# mcu.net
KiCad netlist of a schematic drawn in Altium Designer
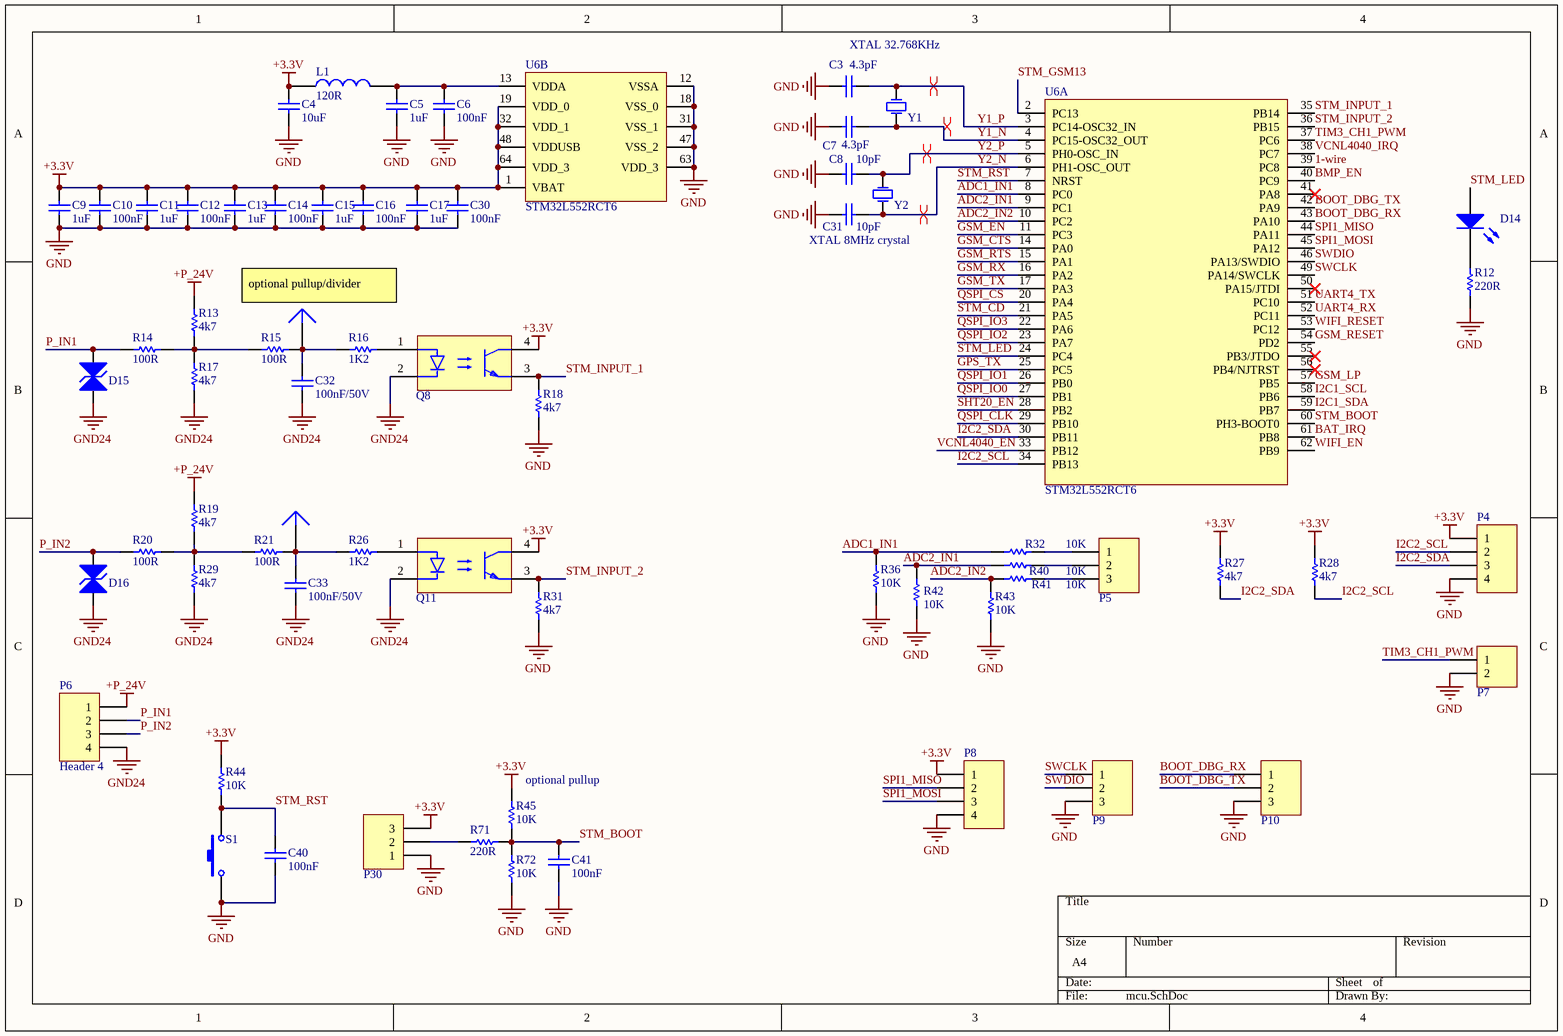
[diagram p0: mcu.SchDoc]

(export (version "E")
  (design (tool "Eeschema 10.0.6"))
  (components
    (comp (ref "C3")
      (value "4.3pF")
      (footprint "C0402")
      (description "Capacitor")
      (fields (field (name "Comment") "Cap 4.3pF"))
      (libsource (lib "integratedLib") (part "Cap 4.3pF"))
    )
    (comp (ref "C4")
      (value "10uF")
      (footprint "C0402")
      (description "Capacitor")
      (fields (field (name "Comment") "Cap 10uF"))
      (libsource (lib "integratedLib") (part "Cap 10uF"))
    )
    (comp (ref "C5")
      (value "1uF")
      (footprint "C0402")
      (description "Capacitor")
      (fields (field (name "Comment") "Cap 1uF"))
      (libsource (lib "integratedLib") (part "Cap 1uF"))
    )
    (comp (ref "C6")
      (value "100nF")
      (footprint "C0402")
      (description "Capacitor")
      (fields (field (name "Comment") "Cap 100nF"))
      (libsource (lib "integratedLib") (part "Cap 100nF"))
    )
    (comp (ref "C7")
      (value "4.3pF")
      (footprint "C0402")
      (description "Capacitor")
      (fields (field (name "Comment") "Cap 4.3pF"))
      (libsource (lib "integratedLib") (part "Cap 4.3pF"))
    )
    (comp (ref "C8")
      (value "10pF")
      (footprint "C0402")
      (description "Capacitor")
      (fields (field (name "Comment") "Cap 10pF"))
      (libsource (lib "integratedLib") (part "Cap 10pF"))
    )
    (comp (ref "C9")
      (value "1uF")
      (footprint "C0402")
      (description "Capacitor")
      (fields (field (name "Comment") "Cap 1uF"))
      (libsource (lib "integratedLib") (part "Cap 1uF"))
    )
    (comp (ref "C10")
      (value "100nF")
      (footprint "C0402")
      (description "Capacitor")
      (fields (field (name "Comment") "Cap 100nF"))
      (libsource (lib "integratedLib") (part "Cap 100nF"))
    )
    (comp (ref "C11")
      (value "1uF")
      (footprint "C0402")
      (description "Capacitor")
      (fields (field (name "Comment") "Cap 1uF"))
      (libsource (lib "integratedLib") (part "Cap 1uF"))
    )
    (comp (ref "C12")
      (value "100nF")
      (footprint "C0402")
      (description "Capacitor")
      (fields (field (name "Comment") "Cap 100nF"))
      (libsource (lib "integratedLib") (part "Cap 100nF"))
    )
    (comp (ref "C13")
      (value "1uF")
      (footprint "C0402")
      (description "Capacitor")
      (fields (field (name "Comment") "Cap 1uF"))
      (libsource (lib "integratedLib") (part "Cap 1uF"))
    )
    (comp (ref "C14")
      (value "100nF")
      (footprint "C0402")
      (description "Capacitor")
      (fields (field (name "Comment") "Cap 100nF"))
      (libsource (lib "integratedLib") (part "Cap 100nF"))
    )
    (comp (ref "C15")
      (value "1uF")
      (footprint "C0402")
      (description "Capacitor")
      (fields (field (name "Comment") "Cap 1uF"))
      (libsource (lib "integratedLib") (part "Cap 1uF"))
    )
    (comp (ref "C16")
      (value "100nF")
      (footprint "C0402")
      (description "Capacitor")
      (fields (field (name "Comment") "Cap 100nF"))
      (libsource (lib "integratedLib") (part "Cap 100nF"))
    )
    (comp (ref "C17")
      (value "1uF")
      (footprint "C0402")
      (description "Capacitor")
      (fields (field (name "Comment") "Cap 1uF"))
      (libsource (lib "integratedLib") (part "Cap 1uF"))
    )
    (comp (ref "C30")
      (value "100nF")
      (footprint "C0402")
      (description "Capacitor")
      (fields (field (name "Comment") "Cap 100nF"))
      (libsource (lib "integratedLib") (part "Cap 100nF"))
    )
    (comp (ref "C31")
      (value "10pF")
      (footprint "C0402")
      (description "Capacitor")
      (fields (field (name "Comment") "Cap 10pF"))
      (libsource (lib "integratedLib") (part "Cap 10pF"))
    )
    (comp (ref "C32")
      (value "100nF/50V")
      (footprint "C1206")
      (description "Capacitor")
      (fields (field (name "Comment") "Cap 100nF/50V"))
      (libsource (lib "integratedLib") (part "Cap 100nF/50V"))
    )
    (comp (ref "C33")
      (value "100nF/50V")
      (footprint "C1206")
      (description "Capacitor")
      (fields (field (name "Comment") "Cap 100nF/50V"))
      (libsource (lib "integratedLib") (part "Cap 100nF/50V"))
    )
    (comp (ref "C40")
      (value "100nF")
      (footprint "C0402")
      (description "Capacitor")
      (fields (field (name "Comment") "Cap 100nF"))
      (libsource (lib "integratedLib") (part "Cap 100nF"))
    )
    (comp (ref "C41")
      (value "100nF")
      (footprint "C0402")
      (description "Capacitor")
      (fields (field (name "Comment") "Cap 100nF"))
      (libsource (lib "integratedLib") (part "Cap 100nF"))
    )
    (comp (ref "D14")
      (value "LED")
      (footprint "0603LedRed")
      (description "Typical RED GaAs LED")
      (fields (field (name "PUBLISHER") "Altium Limited"))
      (libsource (lib "integratedLib") (part "LED"))
    )
    (comp (ref "D15")
      (value "TVS Bidirectional")
      (footprint "SMA")
      (description "SMAJ40CA")
      (fields (field (name "PUBLISHER") "Altium Limited"))
      (libsource (lib "integratedLib") (part "TVS_bidirectional"))
    )
    (comp (ref "D16")
      (value "TVS Bidirectional")
      (footprint "SMA")
      (description "SMAJ40CA")
      (fields (field (name "PUBLISHER") "Altium Limited"))
      (libsource (lib "integratedLib") (part "TVS_bidirectional"))
    )
    (comp (ref "L1")
      (value "120R")
      (footprint "0805FerriteBead")
      (description "Ferrite bead")
      (fields (field (name "PUBLISHER") "Altium Limited"))
      (libsource (lib "integratedLib") (part "Ferrite bead 120R"))
    )
    (comp (ref "P4")
      (value "Header 4")
      (footprint "HDR1X4")
      (description "Header, 4-Pin")
      (fields (field (name "PUBLISHER") "Altium Limited"))
      (libsource (lib "integratedLib") (part "Header 4"))
    )
    (comp (ref "P5")
      (value "Header 3")
      (footprint "HDR1X3")
      (description "Header, 3-Pin")
      (fields (field (name "PUBLISHER") "Altium Limited"))
      (libsource (lib "integratedLib") (part "Header 3"))
    )
    (comp (ref "P6")
      (value "Header 4")
      (footprint "HDR1X4")
      (description "Header, 4-Pin")
      (fields (field (name "PUBLISHER") "Altium Limited"))
      (libsource (lib "") (part "Header 4_1"))
    )
    (comp (ref "P7")
      (value "Header 2")
      (footprint "HDR1X2")
      (description "Header, 2-Pin")
      (fields (field (name "PUBLISHER") "Altium Limited"))
      (libsource (lib "integratedLib") (part "Header 2"))
    )
    (comp (ref "P8")
      (value "Header 4")
      (footprint "HDR1X4")
      (description "Header, 4-Pin")
      (fields (field (name "PUBLISHER") "Altium Limited"))
      (libsource (lib "integratedLib") (part "Header 4"))
    )
    (comp (ref "P9")
      (value "Header 3")
      (footprint "HDR1X3")
      (description "Header, 3-Pin")
      (fields (field (name "PUBLISHER") "Altium Limited"))
      (libsource (lib "integratedLib") (part "Header 3"))
    )
    (comp (ref "P10")
      (value "Header 3")
      (footprint "HDR1X3")
      (description "Header, 3-Pin")
      (fields (field (name "PUBLISHER") "Altium Limited"))
      (libsource (lib "integratedLib") (part "Header 3"))
    )
    (comp (ref "P23")
      (value "Plug")
      (footprint "pin smd")
      (fields (field (name "PUBLISHER") "Altium Limited"))
      (libsource (lib "integratedLib") (part "Plug"))
    )
    (comp (ref "P24")
      (value "Plug")
      (footprint "pin smd")
      (fields (field (name "PUBLISHER") "Altium Limited"))
      (libsource (lib "integratedLib") (part "Plug"))
    )
    (comp (ref "P30")
      (value "Header 3")
      (footprint "HDR1X3")
      (description "Header, 3-Pin")
      (fields (field (name "PUBLISHER") "Altium Limited"))
      (libsource (lib "") (part "Header 3_1"))
    )
    (comp (ref "Q8")
      (value "TLP291")
      (footprint "SO4")
      (description "OPTO  TLP291")
      (libsource (lib "integratedLib") (part "TLP291"))
    )
    (comp (ref "Q11")
      (value "TLP291")
      (footprint "SO4")
      (description "OPTO  TLP291")
      (libsource (lib "integratedLib") (part "TLP291"))
    )
    (comp (ref "R12")
      (value "220R")
      (footprint "R0402")
      (description "Resistor")
      (fields (field (name "Comment") "Res_220R"))
      (libsource (lib "integratedLib") (part "Res_220R"))
    )
    (comp (ref "R13")
      (value "4k7")
      (footprint "R0805")
      (description "Resistor")
      (fields (field (name "Comment") "Res_4k7"))
      (libsource (lib "integratedLib") (part "Res_4k7"))
    )
    (comp (ref "R14")
      (value "100R")
      (footprint "R0805")
      (description "Resistor")
      (fields (field (name "Comment") "Res_100R"))
      (libsource (lib "integratedLib") (part "Res_100R"))
    )
    (comp (ref "R15")
      (value "100R")
      (footprint "R0805")
      (description "Resistor")
      (fields (field (name "Comment") "Res_100R"))
      (libsource (lib "integratedLib") (part "Res_100R"))
    )
    (comp (ref "R16")
      (value "1K2")
      (footprint "R0805")
      (description "Resistor")
      (fields (field (name "Comment") "Res_1K2"))
      (libsource (lib "integratedLib") (part "Res_1K2"))
    )
    (comp (ref "R17")
      (value "4k7")
      (footprint "R0805")
      (description "Resistor")
      (fields (field (name "Comment") "Res_4k7"))
      (libsource (lib "integratedLib") (part "Res_4k7"))
    )
    (comp (ref "R18")
      (value "4k7")
      (footprint "R0402")
      (description "Resistor")
      (fields (field (name "Comment") "Res_4k7"))
      (libsource (lib "integratedLib") (part "Res_4k7"))
    )
    (comp (ref "R19")
      (value "4k7")
      (footprint "R0805")
      (description "Resistor")
      (fields (field (name "Comment") "Res_4k7"))
      (libsource (lib "integratedLib") (part "Res_4k7"))
    )
    (comp (ref "R20")
      (value "100R")
      (footprint "R0805")
      (description "Resistor")
      (fields (field (name "Comment") "Res_100R"))
      (libsource (lib "integratedLib") (part "Res_100R"))
    )
    (comp (ref "R21")
      (value "100R")
      (footprint "R0805")
      (description "Resistor")
      (fields (field (name "Comment") "Res_100R"))
      (libsource (lib "integratedLib") (part "Res_100R"))
    )
    (comp (ref "R26")
      (value "1K2")
      (footprint "R0805")
      (description "Resistor")
      (fields (field (name "Comment") "Res_1K2"))
      (libsource (lib "integratedLib") (part "Res_1K2"))
    )
    (comp (ref "R27")
      (value "4k7")
      (footprint "R0402")
      (description "Resistor")
      (fields (field (name "Comment") "Res_4k7"))
      (libsource (lib "integratedLib") (part "Res_4k7"))
    )
    (comp (ref "R28")
      (value "4k7")
      (footprint "R0402")
      (description "Resistor")
      (fields (field (name "Comment") "Res_4k7"))
      (libsource (lib "integratedLib") (part "Res_4k7"))
    )
    (comp (ref "R29")
      (value "4k7")
      (footprint "R0805")
      (description "Resistor")
      (fields (field (name "Comment") "Res_4k7"))
      (libsource (lib "integratedLib") (part "Res_4k7"))
    )
    (comp (ref "R31")
      (value "4k7")
      (footprint "R0402")
      (description "Resistor")
      (fields (field (name "Comment") "Res_4k7"))
      (libsource (lib "integratedLib") (part "Res_4k7"))
    )
    (comp (ref "R32")
      (value "10K")
      (footprint "R0402")
      (description "Resistor")
      (fields (field (name "Comment") "Res_10K"))
      (libsource (lib "integratedLib") (part "Res_10K"))
    )
    (comp (ref "R36")
      (value "10K")
      (footprint "R0402")
      (description "Resistor")
      (fields (field (name "Comment") "Res_10K"))
      (libsource (lib "integratedLib") (part "Res_10K"))
    )
    (comp (ref "R40")
      (value "10K")
      (footprint "R0402")
      (description "Resistor")
      (fields (field (name "Comment") "Res_10K"))
      (libsource (lib "integratedLib") (part "Res_10K"))
    )
    (comp (ref "R41")
      (value "10K")
      (footprint "R0402")
      (description "Resistor")
      (fields (field (name "Comment") "Res_10K"))
      (libsource (lib "integratedLib") (part "Res_10K"))
    )
    (comp (ref "R42")
      (value "10K")
      (footprint "R0402")
      (description "Resistor")
      (fields (field (name "Comment") "Res_10K"))
      (libsource (lib "integratedLib") (part "Res_10K"))
    )
    (comp (ref "R43")
      (value "10K")
      (footprint "R0402")
      (description "Resistor")
      (fields (field (name "Comment") "Res_10K"))
      (libsource (lib "integratedLib") (part "Res_10K"))
    )
    (comp (ref "R44")
      (value "10K")
      (footprint "R0402")
      (description "Resistor")
      (fields (field (name "Comment") "Res_10K"))
      (libsource (lib "integratedLib") (part "Res_10K"))
    )
    (comp (ref "R45")
      (value "10K")
      (footprint "R0402")
      (description "Resistor")
      (fields (field (name "Comment") "Res_10K"))
      (libsource (lib "integratedLib") (part "Res_10K"))
    )
    (comp (ref "R71")
      (value "220R")
      (footprint "R0402")
      (description "Resistor")
      (fields (field (name "Comment") "Res_220R"))
      (libsource (lib "integratedLib") (part "Res_220R"))
    )
    (comp (ref "R72")
      (value "10K")
      (footprint "R0402")
      (description "Resistor")
      (fields (field (name "Comment") "Res_10K"))
      (libsource (lib "integratedLib") (part "Res_10K"))
    )
    (comp (ref "S1")
      (value "switch")
      (footprint "TACK SWITCH 2-PAD")
      (description "Switch")
      (fields (field (name "PUBLISHER") "Altium Limited"))
      (libsource (lib "integratedLib") (part "switch"))
    )
    (comp (ref "U6")
      (value "STM32L552RCT6")
      (footprint "LQFP64")
      (description "Arm Cortex-M33 with Trust Zone, MCU 110 MHz with 512K Flash 256K Ram memory LQFP64")
      (fields (field (name "MANUFACTURER") "STMicroelectronics") (field (name "PARTNUMBER") "STM32L152CCU6"))
      (libsource (lib "integratedLib") (part "STM32L552RCT6"))
    )
    (comp (ref "Y1")
      (value "XTAL 32.768KHz")
      (footprint "XTAL_FC-13A")
      (description "XTAL 32.768KHz crystal")
      (fields (field (name "PUBLISHER") "Altium Limited"))
      (libsource (lib "integratedLib") (part "XTAL 32.768KHz"))
    )
    (comp (ref "Y2")
      (value "XTAL 8MHz crystal")
      (footprint "XTAL500X320X120")
      (description "TXC Corp 7A08000001")
      (fields (field (name "PUBLISHER") "Altium Limited"))
      (libsource (lib "integratedLib") (part "XTAL 8MHz"))
    )
  )
  (nets
    (net (code "1") (name "+3.3V") (class "Default")
      (node (ref "C10") (pin "1") (pinfunction "1_1") (pintype "passive"))
      (node (ref "C11") (pin "2") (pinfunction "2_2") (pintype "passive"))
      (node (ref "C12") (pin "1") (pinfunction "1_1") (pintype "passive"))
      (node (ref "C13") (pin "2") (pinfunction "2_2") (pintype "passive"))
      (node (ref "C14") (pin "1") (pinfunction "1_1") (pintype "passive"))
      (node (ref "C15") (pin "2") (pinfunction "2_2") (pintype "passive"))
      (node (ref "C16") (pin "1") (pinfunction "1_1") (pintype "passive"))
      (node (ref "C17") (pin "2") (pinfunction "2_2") (pintype "passive"))
      (node (ref "C30") (pin "1") (pinfunction "1_1") (pintype "passive"))
      (node (ref "C4") (pin "2") (pinfunction "2_2") (pintype "passive"))
      (node (ref "C9") (pin "2") (pinfunction "2_2") (pintype "passive"))
      (node (ref "L1") (pin "1") (pinfunction "1_1") (pintype "passive"))
      (node (ref "P30") (pin "3") (pinfunction "3_3") (pintype "passive"))
      (node (ref "P4") (pin "1") (pinfunction "1_1") (pintype "passive"))
      (node (ref "P8") (pin "1") (pinfunction "1_1") (pintype "passive"))
      (node (ref "Q11") (pin "4") (pinfunction "C_4") (pintype "passive"))
      (node (ref "Q8") (pin "4") (pinfunction "C_4") (pintype "passive"))
      (node (ref "R27") (pin "2") (pinfunction "2_2") (pintype "passive"))
      (node (ref "R28") (pin "2") (pinfunction "2_2") (pintype "passive"))
      (node (ref "R44") (pin "2") (pinfunction "2_2") (pintype "passive"))
      (node (ref "R45") (pin "2") (pinfunction "2_2") (pintype "passive"))
      (node (ref "U6") (pin "1") (pinfunction "VBAT_1") (pintype "power_in"))
      (node (ref "U6") (pin "19") (pinfunction "VDD_0_19") (pintype "power_in"))
      (node (ref "U6") (pin "32") (pinfunction "VDD_1_32") (pintype "power_in"))
      (node (ref "U6") (pin "48") (pinfunction "VDDUSB_48") (pintype "power_in"))
      (node (ref "U6") (pin "64") (pinfunction "VDD_3_64") (pintype "power_in"))
    )
    (net (code "2") (name "+P_24V") (class "Default")
      (node (ref "P6") (pin "1") (pinfunction "1_1") (pintype "passive"))
      (node (ref "R13") (pin "2") (pinfunction "2_2") (pintype "passive"))
      (node (ref "R19") (pin "2") (pinfunction "2_2") (pintype "passive"))
    )
    (net (code "3") (name "/1-wire") (class "Default")
      (node (ref "U6") (pin "39") (pinfunction "PC8_39") (pintype "power_in"))
    )
    (net (code "4") (name "/ADC1_IN1") (class "Default")
      (node (ref "R32") (pin "1") (pinfunction "1_1") (pintype "passive"))
      (node (ref "R36") (pin "2") (pinfunction "2_2") (pintype "passive"))
      (node (ref "U6") (pin "8") (pinfunction "PC0_8") (pintype "power_in"))
    )
    (net (code "5") (name "/ADC2_IN1") (class "Default")
      (node (ref "R40") (pin "1") (pinfunction "1_1") (pintype "passive"))
      (node (ref "R42") (pin "2") (pinfunction "2_2") (pintype "passive"))
      (node (ref "U6") (pin "9") (pinfunction "PC1_9") (pintype "power_in"))
    )
    (net (code "6") (name "/ADC2_IN2") (class "Default")
      (node (ref "R41") (pin "1") (pinfunction "1_1") (pintype "passive"))
      (node (ref "R43") (pin "2") (pinfunction "2_2") (pintype "passive"))
      (node (ref "U6") (pin "10") (pinfunction "PC2_10") (pintype "power_in"))
    )
    (net (code "7") (name "/BAT_IRQ") (class "Default")
      (node (ref "U6") (pin "61") (pinfunction "PB8_61") (pintype "power_in"))
    )
    (net (code "8") (name "/BMP_EN") (class "Default")
      (node (ref "U6") (pin "40") (pinfunction "PC9_40") (pintype "power_in"))
    )
    (net (code "9") (name "/BOOT_DBG_RX") (class "Default")
      (node (ref "P10") (pin "1") (pinfunction "1_1") (pintype "passive"))
      (node (ref "U6") (pin "43") (pinfunction "PA10_43") (pintype "power_in"))
    )
    (net (code "10") (name "/BOOT_DBG_TX") (class "Default")
      (node (ref "P10") (pin "2") (pinfunction "2_2") (pintype "passive"))
      (node (ref "U6") (pin "42") (pinfunction "PA9_42") (pintype "power_in"))
    )
    (net (code "11") (name "/GPS_TX") (class "Default")
      (node (ref "U6") (pin "25") (pinfunction "PC5_25") (pintype "power_in"))
    )
    (net (code "12") (name "/GSM_CTS") (class "Default")
      (node (ref "U6") (pin "14") (pinfunction "PA0_14") (pintype "power_in"))
    )
    (net (code "13") (name "/GSM_EN") (class "Default")
      (node (ref "U6") (pin "11") (pinfunction "PC3_11") (pintype "power_in"))
    )
    (net (code "14") (name "/GSM_LP") (class "Default")
      (node (ref "U6") (pin "57") (pinfunction "PB5_57") (pintype "power_in"))
    )
    (net (code "15") (name "/GSM_RESET") (class "Default")
      (node (ref "U6") (pin "54") (pinfunction "PD2_54") (pintype "power_in"))
    )
    (net (code "16") (name "/GSM_RTS") (class "Default")
      (node (ref "U6") (pin "15") (pinfunction "PA1_15") (pintype "power_in"))
    )
    (net (code "17") (name "/GSM_RX") (class "Default")
      (node (ref "U6") (pin "16") (pinfunction "PA2_16") (pintype "power_in"))
    )
    (net (code "18") (name "/GSM_TX") (class "Default")
      (node (ref "U6") (pin "17") (pinfunction "PA3_17") (pintype "power_in"))
    )
    (net (code "19") (name "/I2C1_SCL") (class "Default")
      (node (ref "U6") (pin "58") (pinfunction "PB6_58") (pintype "power_in"))
    )
    (net (code "20") (name "/I2C1_SDA") (class "Default")
      (node (ref "U6") (pin "59") (pinfunction "PB7_59") (pintype "power_in"))
    )
    (net (code "21") (name "/I2C2_SCL") (class "Default")
      (node (ref "P4") (pin "2") (pinfunction "2_2") (pintype "passive"))
      (node (ref "R28") (pin "1") (pinfunction "1_1") (pintype "passive"))
      (node (ref "U6") (pin "34") (pinfunction "PB13_34") (pintype "power_in"))
    )
    (net (code "22") (name "/I2C2_SDA") (class "Default")
      (node (ref "P4") (pin "3") (pinfunction "3_3") (pintype "passive"))
      (node (ref "R27") (pin "1") (pinfunction "1_1") (pintype "passive"))
      (node (ref "U6") (pin "30") (pinfunction "PB11_30") (pintype "power_in"))
    )
    (net (code "23") (name "/P_IN1") (class "Default")
      (node (ref "D15") (pin "2") (pintype "passive"))
      (node (ref "P6") (pin "2") (pinfunction "2_2") (pintype "passive"))
      (node (ref "R14") (pin "1") (pinfunction "1_1") (pintype "passive"))
    )
    (net (code "24") (name "/P_IN2") (class "Default")
      (node (ref "D16") (pin "2") (pintype "passive"))
      (node (ref "P6") (pin "3") (pinfunction "3_3") (pintype "passive"))
      (node (ref "R20") (pin "1") (pinfunction "1_1") (pintype "passive"))
    )
    (net (code "25") (name "/QSPI_CLK") (class "Default")
      (node (ref "U6") (pin "29") (pinfunction "PB10_29") (pintype "power_in"))
    )
    (net (code "26") (name "/QSPI_CS") (class "Default")
      (node (ref "U6") (pin "20") (pinfunction "PA4_20") (pintype "power_in"))
    )
    (net (code "27") (name "/QSPI_IO0") (class "Default")
      (node (ref "U6") (pin "27") (pinfunction "PB1_27") (pintype "power_in"))
    )
    (net (code "28") (name "/QSPI_IO1") (class "Default")
      (node (ref "U6") (pin "26") (pinfunction "PB0_26") (pintype "power_in"))
    )
    (net (code "29") (name "/QSPI_IO2") (class "Default")
      (node (ref "U6") (pin "23") (pinfunction "PA7_23") (pintype "power_in"))
    )
    (net (code "30") (name "/QSPI_IO3") (class "Default")
      (node (ref "U6") (pin "22") (pinfunction "PA6_22") (pintype "power_in"))
    )
    (net (code "31") (name "/SHT20_EN") (class "Default")
      (node (ref "U6") (pin "28") (pinfunction "PB2_28") (pintype "power_in"))
    )
    (net (code "32") (name "/SPI1_MISO") (class "Default")
      (node (ref "P8") (pin "2") (pinfunction "2_2") (pintype "passive"))
      (node (ref "U6") (pin "44") (pinfunction "PA11_44") (pintype "power_in"))
    )
    (net (code "33") (name "/SPI1_MOSI") (class "Default")
      (node (ref "P8") (pin "3") (pinfunction "3_3") (pintype "passive"))
      (node (ref "U6") (pin "45") (pinfunction "PA12_45") (pintype "power_in"))
    )
    (net (code "34") (name "/STM_BOOT") (class "Default")
      (node (ref "C41") (pin "2") (pinfunction "2_2") (pintype "passive"))
      (node (ref "R45") (pin "1") (pinfunction "1_1") (pintype "passive"))
      (node (ref "R71") (pin "2") (pinfunction "2_2") (pintype "passive"))
      (node (ref "R72") (pin "2") (pinfunction "2_2") (pintype "passive"))
      (node (ref "U6") (pin "60") (pinfunction "PH3-BOOT0_60") (pintype "power_in"))
    )
    (net (code "35") (name "/STM_CD") (class "Default")
      (node (ref "U6") (pin "21") (pinfunction "PA5_21") (pintype "power_in"))
    )
    (net (code "36") (name "/STM_GSM13") (class "Default")
      (node (ref "U6") (pin "2") (pinfunction "PC13_2") (pintype "power_in"))
    )
    (net (code "37") (name "/STM_INPUT_1") (class "Default")
      (node (ref "Q8") (pin "3") (pinfunction "E_3") (pintype "passive"))
      (node (ref "R18") (pin "2") (pinfunction "2_2") (pintype "passive"))
      (node (ref "U6") (pin "35") (pinfunction "PB14_35") (pintype "power_in"))
    )
    (net (code "38") (name "/STM_INPUT_2") (class "Default")
      (node (ref "Q11") (pin "3") (pinfunction "E_3") (pintype "passive"))
      (node (ref "R31") (pin "2") (pinfunction "2_2") (pintype "passive"))
      (node (ref "U6") (pin "36") (pinfunction "PB15_36") (pintype "power_in"))
    )
    (net (code "39") (name "/STM_LED") (class "Default")
      (node (ref "D14") (pin "1") (pinfunction "A_1") (pintype "passive"))
      (node (ref "U6") (pin "24") (pinfunction "PC4_24") (pintype "power_in"))
    )
    (net (code "40") (name "/STM_RST") (class "Default")
      (node (ref "C40") (pin "2") (pinfunction "2_2") (pintype "passive"))
      (node (ref "R44") (pin "1") (pinfunction "1_1") (pintype "passive"))
      (node (ref "S1") (pin "2") (pinfunction "2_2") (pintype "passive"))
      (node (ref "U6") (pin "7") (pinfunction "NRST_7") (pintype "power_in"))
    )
    (net (code "41") (name "/SWCLK") (class "Default")
      (node (ref "P9") (pin "1") (pinfunction "1_1") (pintype "passive"))
      (node (ref "U6") (pin "49") (pinfunction "PA14/SWCLK_49") (pintype "power_in"))
    )
    (net (code "42") (name "/SWDIO") (class "Default")
      (node (ref "P9") (pin "2") (pinfunction "2_2") (pintype "passive"))
      (node (ref "U6") (pin "46") (pinfunction "PA13/SWDIO_46") (pintype "power_in"))
    )
    (net (code "43") (name "/TIM3_CH1_PWM") (class "Default")
      (node (ref "P7") (pin "1") (pinfunction "1_1") (pintype "passive"))
      (node (ref "U6") (pin "37") (pinfunction "PC6_37") (pintype "power_in"))
    )
    (net (code "44") (name "/UART4_RX") (class "Default")
      (node (ref "U6") (pin "52") (pinfunction "PC11_52") (pintype "power_in"))
    )
    (net (code "45") (name "/UART4_TX") (class "Default")
      (node (ref "U6") (pin "51") (pinfunction "PC10_51") (pintype "power_in"))
    )
    (net (code "46") (name "/VCNL4040_EN") (class "Default")
      (node (ref "U6") (pin "33") (pinfunction "PB12_33") (pintype "power_in"))
    )
    (net (code "47") (name "/VCNL4040_IRQ") (class "Default")
      (node (ref "U6") (pin "38") (pinfunction "PC7_38") (pintype "power_in"))
    )
    (net (code "48") (name "/WIFI_EN") (class "Default")
      (node (ref "U6") (pin "62") (pinfunction "PB9_62") (pintype "power_in"))
    )
    (net (code "49") (name "/WIFI_RESET") (class "Default")
      (node (ref "U6") (pin "53") (pinfunction "PC12_53") (pintype "power_in"))
    )
    (net (code "50") (name "/Y1_N") (class "Default")
      (node (ref "C7") (pin "1") (pinfunction "1_1") (pintype "passive"))
      (node (ref "U6") (pin "4") (pinfunction "PC15-OSC32_OUT_4") (pintype "power_in"))
      (node (ref "Y1") (pin "1") (pinfunction "OSC1_1") (pintype "passive"))
    )
    (net (code "51") (name "/Y1_P") (class "Default")
      (node (ref "C3") (pin "1") (pinfunction "1_1") (pintype "passive"))
      (node (ref "U6") (pin "3") (pinfunction "PC14-OSC32_IN_3") (pintype "power_in"))
      (node (ref "Y1") (pin "2") (pinfunction "OSC2_2") (pintype "passive"))
    )
    (net (code "52") (name "/Y2_N") (class "Default")
      (node (ref "C31") (pin "1") (pinfunction "1_1") (pintype "passive"))
      (node (ref "U6") (pin "6") (pinfunction "PH1-OSC_OUT_6") (pintype "power_in"))
      (node (ref "Y2") (pin "1") (pinfunction "OSC1_1") (pintype "passive"))
    )
    (net (code "53") (name "/Y2_P") (class "Default")
      (node (ref "C8") (pin "1") (pinfunction "1_1") (pintype "passive"))
      (node (ref "U6") (pin "5") (pinfunction "PH0-OSC_IN_5") (pintype "power_in"))
      (node (ref "Y2") (pin "2") (pinfunction "OSC2_2") (pintype "passive"))
    )
    (net (code "54") (name "GND") (class "Default")
      (node (ref "C10") (pin "2") (pinfunction "2_2") (pintype "passive"))
      (node (ref "C11") (pin "1") (pinfunction "1_1") (pintype "passive"))
      (node (ref "C12") (pin "2") (pinfunction "2_2") (pintype "passive"))
      (node (ref "C13") (pin "1") (pinfunction "1_1") (pintype "passive"))
      (node (ref "C14") (pin "2") (pinfunction "2_2") (pintype "passive"))
      (node (ref "C15") (pin "1") (pinfunction "1_1") (pintype "passive"))
      (node (ref "C16") (pin "2") (pinfunction "2_2") (pintype "passive"))
      (node (ref "C17") (pin "1") (pinfunction "1_1") (pintype "passive"))
      (node (ref "C3") (pin "2") (pinfunction "2_2") (pintype "passive"))
      (node (ref "C30") (pin "2") (pinfunction "2_2") (pintype "passive"))
      (node (ref "C31") (pin "2") (pinfunction "2_2") (pintype "passive"))
      (node (ref "C4") (pin "1") (pinfunction "1_1") (pintype "passive"))
      (node (ref "C40") (pin "1") (pinfunction "1_1") (pintype "passive"))
      (node (ref "C41") (pin "1") (pinfunction "1_1") (pintype "passive"))
      (node (ref "C5") (pin "1") (pinfunction "1_1") (pintype "passive"))
      (node (ref "C6") (pin "2") (pinfunction "2_2") (pintype "passive"))
      (node (ref "C7") (pin "2") (pinfunction "2_2") (pintype "passive"))
      (node (ref "C8") (pin "2") (pinfunction "2_2") (pintype "passive"))
      (node (ref "C9") (pin "1") (pinfunction "1_1") (pintype "passive"))
      (node (ref "P10") (pin "3") (pinfunction "3_3") (pintype "passive"))
      (node (ref "P30") (pin "1") (pinfunction "1_1") (pintype "passive"))
      (node (ref "P4") (pin "4") (pinfunction "4_4") (pintype "passive"))
      (node (ref "P7") (pin "2") (pinfunction "2_2") (pintype "passive"))
      (node (ref "P8") (pin "4") (pinfunction "4_4") (pintype "passive"))
      (node (ref "P9") (pin "3") (pinfunction "3_3") (pintype "passive"))
      (node (ref "R12") (pin "1") (pinfunction "1_1") (pintype "passive"))
      (node (ref "R18") (pin "1") (pinfunction "1_1") (pintype "passive"))
      (node (ref "R31") (pin "1") (pinfunction "1_1") (pintype "passive"))
      (node (ref "R36") (pin "1") (pinfunction "1_1") (pintype "passive"))
      (node (ref "R42") (pin "1") (pinfunction "1_1") (pintype "passive"))
      (node (ref "R43") (pin "1") (pinfunction "1_1") (pintype "passive"))
      (node (ref "R72") (pin "1") (pinfunction "1_1") (pintype "passive"))
      (node (ref "S1") (pin "1") (pinfunction "1_1") (pintype "passive"))
      (node (ref "U6") (pin "12") (pinfunction "VSSA_12") (pintype "power_in"))
      (node (ref "U6") (pin "18") (pinfunction "VSS_0_18") (pintype "power_in"))
      (node (ref "U6") (pin "31") (pinfunction "VSS_1_31") (pintype "power_in"))
      (node (ref "U6") (pin "47") (pinfunction "VSS_2_47") (pintype "power_in"))
      (node (ref "U6") (pin "63") (pinfunction "VDD_3_63") (pintype "power_in"))
    )
    (net (code "55") (name "GND24") (class "Default")
      (node (ref "C32") (pin "1") (pinfunction "1_1") (pintype "passive"))
      (node (ref "C33") (pin "1") (pinfunction "1_1") (pintype "passive"))
      (node (ref "D15") (pin "1") (pintype "passive"))
      (node (ref "D16") (pin "1") (pintype "passive"))
      (node (ref "P6") (pin "4") (pinfunction "4_4") (pintype "passive"))
      (node (ref "Q11") (pin "2") (pinfunction "C_2") (pintype "passive"))
      (node (ref "Q8") (pin "2") (pinfunction "C_2") (pintype "passive"))
      (node (ref "R17") (pin "1") (pinfunction "1_1") (pintype "passive"))
      (node (ref "R29") (pin "1") (pinfunction "1_1") (pintype "passive"))
    )
    (net (code "56") (name "Net-(C32-Pad2)") (class "Default")
      (node (ref "C32") (pin "2") (pinfunction "2_2") (pintype "passive"))
      (node (ref "P23") (pin "1") (pinfunction "1_1") (pintype "passive"))
      (node (ref "R15") (pin "2") (pinfunction "2_2") (pintype "passive"))
      (node (ref "R16") (pin "1") (pinfunction "1_1") (pintype "passive"))
    )
    (net (code "57") (name "Net-(C33-Pad2)") (class "Default")
      (node (ref "C33") (pin "2") (pinfunction "2_2") (pintype "passive"))
      (node (ref "P24") (pin "1") (pinfunction "1_1") (pintype "passive"))
      (node (ref "R21") (pin "2") (pinfunction "2_2") (pintype "passive"))
      (node (ref "R26") (pin "1") (pinfunction "1_1") (pintype "passive"))
    )
    (net (code "58") (name "Net-(D14-K)") (class "Default")
      (node (ref "D14") (pin "2") (pinfunction "K_2") (pintype "passive"))
      (node (ref "R12") (pin "2") (pinfunction "2_2") (pintype "passive"))
    )
    (net (code "59") (name "Net-(P5-Pad1)") (class "Default")
      (node (ref "P5") (pin "1") (pinfunction "1_1") (pintype "passive"))
      (node (ref "R32") (pin "2") (pinfunction "2_2") (pintype "passive"))
    )
    (net (code "60") (name "Net-(P5-Pad2)") (class "Default")
      (node (ref "P5") (pin "2") (pinfunction "2_2") (pintype "passive"))
      (node (ref "R40") (pin "2") (pinfunction "2_2") (pintype "passive"))
    )
    (net (code "61") (name "Net-(P5-Pad3)") (class "Default")
      (node (ref "P5") (pin "3") (pinfunction "3_3") (pintype "passive"))
      (node (ref "R41") (pin "2") (pinfunction "2_2") (pintype "passive"))
    )
    (net (code "62") (name "Net-(P30-Pad2)") (class "Default")
      (node (ref "P30") (pin "2") (pinfunction "2_2") (pintype "passive"))
      (node (ref "R71") (pin "1") (pinfunction "1_1") (pintype "passive"))
    )
    (net (code "63") (name "Net-(Q8-A)") (class "Default")
      (node (ref "Q8") (pin "1") (pinfunction "A_1") (pintype "passive"))
      (node (ref "R16") (pin "2") (pinfunction "2_2") (pintype "passive"))
    )
    (net (code "64") (name "Net-(Q11-A)") (class "Default")
      (node (ref "Q11") (pin "1") (pinfunction "A_1") (pintype "passive"))
      (node (ref "R26") (pin "2") (pinfunction "2_2") (pintype "passive"))
    )
    (net (code "65") (name "Net-(R13-Pad1)") (class "Default")
      (node (ref "R13") (pin "1") (pinfunction "1_1") (pintype "passive"))
      (node (ref "R14") (pin "2") (pinfunction "2_2") (pintype "passive"))
      (node (ref "R15") (pin "1") (pinfunction "1_1") (pintype "passive"))
      (node (ref "R17") (pin "2") (pinfunction "2_2") (pintype "passive"))
    )
    (net (code "66") (name "Net-(R19-Pad1)") (class "Default")
      (node (ref "R19") (pin "1") (pinfunction "1_1") (pintype "passive"))
      (node (ref "R20") (pin "2") (pinfunction "2_2") (pintype "passive"))
      (node (ref "R21") (pin "1") (pinfunction "1_1") (pintype "passive"))
      (node (ref "R29") (pin "2") (pinfunction "2_2") (pintype "passive"))
    )
    (net (code "67") (name "Net-(U6B-VDDA)") (class "Default")
      (node (ref "C5") (pin "2") (pinfunction "2_2") (pintype "passive"))
      (node (ref "C6") (pin "1") (pinfunction "1_1") (pintype "passive"))
      (node (ref "L1") (pin "2") (pinfunction "2_2") (pintype "passive"))
      (node (ref "U6") (pin "13") (pinfunction "VDDA_13") (pintype "power_in"))
    )
    (net (code "68") (name "unconnected-(U6A-PA8-Pad41)") (class "Default")
      (node (ref "U6") (pin "41") (pinfunction "PA8_41") (pintype "power_in+no_connect"))
    )
    (net (code "69") (name "unconnected-(U6A-PA15{slash}JTDI-Pad50)") (class "Default")
      (node (ref "U6") (pin "50") (pinfunction "PA15/JTDI_50") (pintype "power_in+no_connect"))
    )
    (net (code "70") (name "unconnected-(U6A-PB3{slash}JTDO-Pad55)") (class "Default")
      (node (ref "U6") (pin "55") (pinfunction "PB3/JTDO_55") (pintype "power_in+no_connect"))
    )
    (net (code "71") (name "unconnected-(U6A-PB4{slash}NJTRST-Pad56)") (class "Default")
      (node (ref "U6") (pin "56") (pinfunction "PB4/NJTRST_56") (pintype "power_in+no_connect"))
    )
  )
)
